# blinkm_mk2l.net
KiCad netlist of a schematic drawn in EAGLE
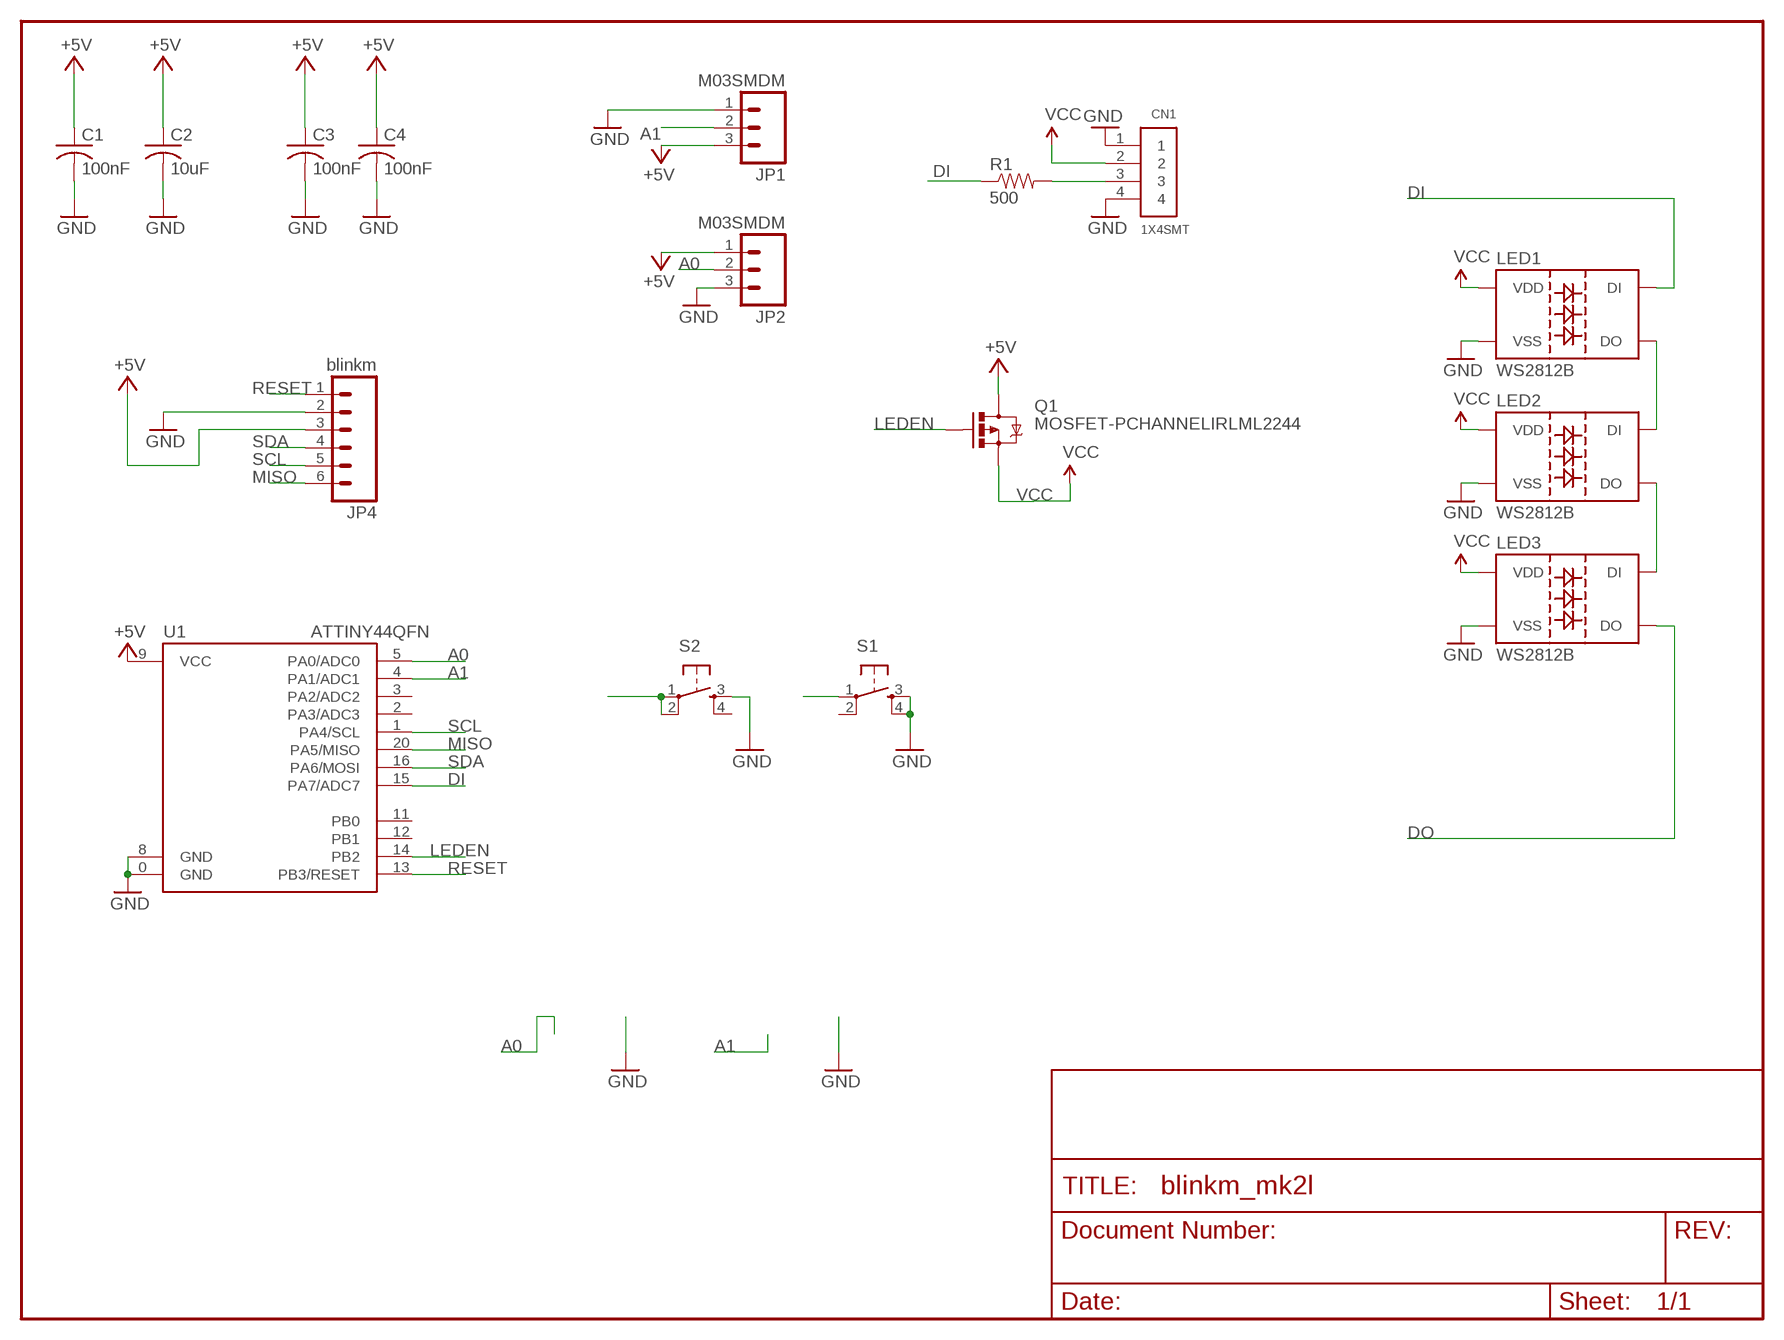
[diagram p0: schematic, sheet 1]

(export (version "E")
  (design (tool "Eeschema 10.0.6"))
  (components
    (comp (ref "C1")
      (value "100nF")
      (footprint "eagle-import:C0603")
      (libsource (lib "eagle-import") (part "C-USC0603"))
    )
    (comp (ref "C2")
      (value "10uF")
      (footprint "eagle-import:C0603")
      (libsource (lib "eagle-import") (part "C-USC0603"))
    )
    (comp (ref "C3")
      (value "100nF")
      (footprint "eagle-import:C0603")
      (libsource (lib "eagle-import") (part "C-USC0603"))
    )
    (comp (ref "C4")
      (value "100nF")
      (footprint "eagle-import:C0603")
      (libsource (lib "eagle-import") (part "C-USC0603"))
    )
    (comp (ref "CN1")
      (value "1X4SMT")
      (footprint "eagle-import:1X4-SMT")
      (libsource (lib "eagle-import") (part "1X4SMT"))
    )
    (comp (ref "JP1")
      (value "M03SMDM")
      (footprint "eagle-import:1X03-SMD-MINIMAL")
      (libsource (lib "eagle-import") (part "M03SMDM"))
    )
    (comp (ref "JP2")
      (value "M03SMDM")
      (footprint "eagle-import:1X03-SMD-MINIMAL")
      (libsource (lib "eagle-import") (part "M03SMDM"))
    )
    (comp (ref "JP4")
      (value "blinkm")
      (footprint "eagle-import:1X06_LOCK")
      (libsource (lib "eagle-import") (part "M06LOCK"))
    )
    (comp (ref "LED1")
      (value "WS2812B")
      (footprint "eagle-import:WS2812B")
      (libsource (lib "eagle-import") (part "WS2812B"))
    )
    (comp (ref "LED2")
      (value "WS2812B")
      (footprint "eagle-import:WS2812B")
      (libsource (lib "eagle-import") (part "WS2812B"))
    )
    (comp (ref "LED3")
      (value "WS2812B")
      (footprint "eagle-import:WS2812B")
      (libsource (lib "eagle-import") (part "WS2812B"))
    )
    (comp (ref "Q1")
      (value "MOSFET-PCHANNELIRLML2244")
      (footprint "eagle-import:SOT23-3")
      (libsource (lib "eagle-import") (part "MOSFET-PCHANNELIRLML2244"))
    )
    (comp (ref "R1")
      (value "500")
      (footprint "eagle-import:0603-RES")
      (libsource (lib "eagle-import") (part "RESISTOR0603"))
    )
    (comp (ref "S1")
      (value "TAC_SWITCHSMD")
      (footprint "eagle-import:TACTILE_SWITCH_SMD")
      (libsource (lib "eagle-import") (part "TAC_SWITCHSMD"))
    )
    (comp (ref "S2")
      (value "TAC_SWITCHSMD")
      (footprint "eagle-import:TACTILE_SWITCH_SMD")
      (libsource (lib "eagle-import") (part "TAC_SWITCHSMD"))
    )
    (comp (ref "U1")
      (value "ATTINY44QFN")
      (footprint "eagle-import:QFN20")
      (libsource (lib "eagle-import") (part "ATTINY24QFN"))
    )
  )
  (nets
    (net (code "1") (name "+5V") (class "Default")
      (node (ref "C1") (pin "1") (pinfunction "1_1") (pintype "passive"))
      (node (ref "C2") (pin "1") (pinfunction "1_1") (pintype "passive"))
      (node (ref "C3") (pin "1") (pinfunction "1_1") (pintype "passive"))
      (node (ref "C4") (pin "1") (pinfunction "1_1") (pintype "passive"))
      (node (ref "JP1") (pin "3") (pinfunction "3_3") (pintype "passive"))
      (node (ref "JP2") (pin "1") (pinfunction "1_1") (pintype "passive"))
      (node (ref "JP4") (pin "3") (pinfunction "3_3") (pintype "passive"))
      (node (ref "Q1") (pin "3") (pinfunction "D_3") (pintype "passive"))
      (node (ref "U1") (pin "9") (pinfunction "VCC_9") (pintype "bidirectional"))
    )
    (net (code "2") (name "/A0") (class "Default")
      (node (ref "JP2") (pin "2") (pinfunction "2_2") (pintype "passive"))
      (node (ref "S2") (pin "1") (pinfunction "1_1") (pintype "passive"))
      (node (ref "S2") (pin "2") (pinfunction "2_2") (pintype "passive"))
      (node (ref "U1") (pin "5") (pinfunction "PA0/ADC0_5") (pintype "bidirectional"))
    )
    (net (code "3") (name "/A1") (class "Default")
      (node (ref "JP1") (pin "2") (pinfunction "2_2") (pintype "passive"))
      (node (ref "S1") (pin "1") (pinfunction "1_1") (pintype "passive"))
      (node (ref "U1") (pin "4") (pinfunction "PA1/ADC1_4") (pintype "bidirectional"))
    )
    (net (code "4") (name "/DI") (class "Default")
      (node (ref "LED1") (pin "4") (pinfunction "DI_4") (pintype "bidirectional"))
      (node (ref "R1") (pin "1") (pinfunction "1_1") (pintype "passive"))
      (node (ref "U1") (pin "15") (pinfunction "PA7/ADC7_15") (pintype "bidirectional"))
    )
    (net (code "5") (name "/DO") (class "Default")
      (node (ref "LED3") (pin "2") (pinfunction "DO_2") (pintype "bidirectional"))
    )
    (net (code "6") (name "/LEDEN") (class "Default")
      (node (ref "Q1") (pin "1") (pinfunction "G_1") (pintype "passive"))
      (node (ref "U1") (pin "14") (pinfunction "PB2_14") (pintype "bidirectional"))
    )
    (net (code "7") (name "/MISO") (class "Default")
      (node (ref "JP4") (pin "6") (pinfunction "6_6") (pintype "passive"))
      (node (ref "U1") (pin "20") (pinfunction "PA5/MISO_20") (pintype "bidirectional"))
    )
    (net (code "8") (name "/RESET") (class "Default")
      (node (ref "JP4") (pin "1") (pinfunction "1_1") (pintype "passive"))
      (node (ref "U1") (pin "13") (pinfunction "PB3/RESET_13") (pintype "bidirectional"))
    )
    (net (code "9") (name "/SCL") (class "Default")
      (node (ref "JP4") (pin "5") (pinfunction "5_5") (pintype "passive"))
      (node (ref "U1") (pin "1") (pinfunction "PA4/SCL_1") (pintype "bidirectional"))
    )
    (net (code "10") (name "/SDA") (class "Default")
      (node (ref "JP4") (pin "4") (pinfunction "4_4") (pintype "passive"))
      (node (ref "U1") (pin "16") (pinfunction "PA6/MOSI_16") (pintype "bidirectional"))
    )
    (net (code "11") (name "GND") (class "Default")
      (node (ref "C1") (pin "2") (pinfunction "2_2") (pintype "passive"))
      (node (ref "C2") (pin "2") (pinfunction "2_2") (pintype "passive"))
      (node (ref "C3") (pin "2") (pinfunction "2_2") (pintype "passive"))
      (node (ref "C4") (pin "2") (pinfunction "2_2") (pintype "passive"))
      (node (ref "CN1") (pin "1") (pinfunction "1_1") (pintype "bidirectional"))
      (node (ref "CN1") (pin "4") (pinfunction "4_4") (pintype "bidirectional"))
      (node (ref "JP1") (pin "1") (pinfunction "1_1") (pintype "passive"))
      (node (ref "JP2") (pin "3") (pinfunction "3_3") (pintype "passive"))
      (node (ref "JP4") (pin "2") (pinfunction "2_2") (pintype "passive"))
      (node (ref "LED1") (pin "3") (pinfunction "VSS_3") (pintype "bidirectional"))
      (node (ref "LED2") (pin "3") (pinfunction "VSS_3") (pintype "bidirectional"))
      (node (ref "LED3") (pin "3") (pinfunction "VSS_3") (pintype "bidirectional"))
      (node (ref "S1") (pin "3") (pinfunction "3_3") (pintype "passive"))
      (node (ref "S1") (pin "4") (pinfunction "4_4") (pintype "passive"))
      (node (ref "S2") (pin "3") (pinfunction "3_3") (pintype "passive"))
      (node (ref "U1") (pin "0") (pinfunction "GND_0") (pintype "bidirectional"))
      (node (ref "U1") (pin "8") (pinfunction "GND_8") (pintype "bidirectional"))
    )
    (net (code "12") (name "Net-(CN1-Pad3)") (class "Default")
      (node (ref "CN1") (pin "3") (pinfunction "3_3") (pintype "bidirectional"))
      (node (ref "R1") (pin "2") (pinfunction "2_2") (pintype "passive"))
    )
    (net (code "13") (name "Net-(LED1-DO)") (class "Default")
      (node (ref "LED1") (pin "2") (pinfunction "DO_2") (pintype "bidirectional"))
      (node (ref "LED2") (pin "4") (pinfunction "DI_4") (pintype "bidirectional"))
    )
    (net (code "14") (name "Net-(LED2-DO)") (class "Default")
      (node (ref "LED2") (pin "2") (pinfunction "DO_2") (pintype "bidirectional"))
      (node (ref "LED3") (pin "4") (pinfunction "DI_4") (pintype "bidirectional"))
    )
    (net (code "15") (name "VCC") (class "Default")
      (node (ref "CN1") (pin "2") (pinfunction "2_2") (pintype "bidirectional"))
      (node (ref "LED1") (pin "1") (pinfunction "VDD_1") (pintype "bidirectional"))
      (node (ref "LED2") (pin "1") (pinfunction "VDD_1") (pintype "bidirectional"))
      (node (ref "LED3") (pin "1") (pinfunction "VDD_1") (pintype "bidirectional"))
      (node (ref "Q1") (pin "2") (pinfunction "S_2") (pintype "passive"))
    )
    (net (code "16") (name "unconnected-(S1-Pad2)") (class "Default")
      (node (ref "S1") (pin "2") (pinfunction "2_2") (pintype "passive"))
    )
    (net (code "17") (name "unconnected-(S2-Pad4)") (class "Default")
      (node (ref "S2") (pin "4") (pinfunction "4_4") (pintype "passive"))
    )
    (net (code "18") (name "unconnected-(U1-PA2{slash}ADC2-Pad3)") (class "Default")
      (node (ref "U1") (pin "3") (pinfunction "PA2/ADC2_3") (pintype "bidirectional"))
    )
    (net (code "19") (name "unconnected-(U1-PA3{slash}ADC3-Pad2)") (class "Default")
      (node (ref "U1") (pin "2") (pinfunction "PA3/ADC3_2") (pintype "bidirectional"))
    )
    (net (code "20") (name "unconnected-(U1-PB0-Pad11)") (class "Default")
      (node (ref "U1") (pin "11") (pinfunction "PB0_11") (pintype "bidirectional"))
    )
    (net (code "21") (name "unconnected-(U1-PB1-Pad12)") (class "Default")
      (node (ref "U1") (pin "12") (pinfunction "PB1_12") (pintype "bidirectional"))
    )
  )
)
